# design.net
KiCad netlist of a schematic drawn in Altium Designer
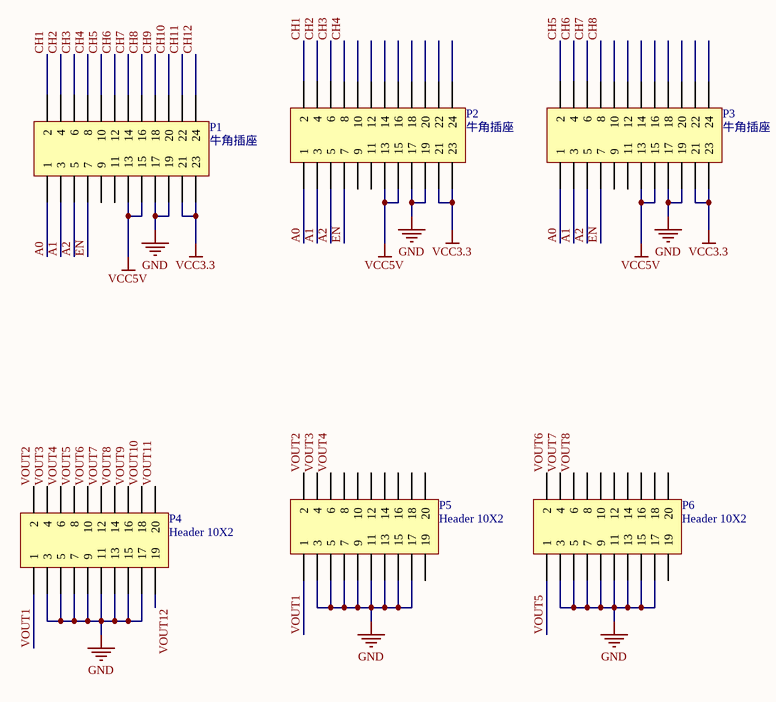
[diagram p0: 数粒机转接板.SchDoc]

(export (version "E")
  (design (tool "Eeschema 10.0.6"))
  (components
    (comp (ref "P1")
      (value "牛角插座")
      (footprint "niujiaocha24p")
      (description "Header, 12-Pin, Dual row")
      (fields (field (name "PUBLISHER") "Altium Limited"))
      (libsource (lib "Miscellaneous Connectors") (part "Header 12X2"))
    )
    (comp (ref "P2")
      (value "牛角插座")
      (footprint "niujiaocha24p")
      (description "Header, 12-Pin, Dual row")
      (fields (field (name "PUBLISHER") "Altium Limited"))
      (libsource (lib "Miscellaneous Connectors") (part "Header 12X2"))
    )
    (comp (ref "P3")
      (value "牛角插座")
      (footprint "niujiaocha24p")
      (description "Header, 12-Pin, Dual row")
      (fields (field (name "PUBLISHER") "Altium Limited"))
      (libsource (lib "Miscellaneous Connectors") (part "Header 12X2"))
    )
    (comp (ref "P4")
      (value "Header 10X2")
      (footprint "niujiaocha20p")
      (description "Header, 10-Pin, Dual row")
      (fields (field (name "PUBLISHER") "Altium Limited"))
      (libsource (lib "Miscellaneous Connectors") (part "Header 10X2"))
    )
    (comp (ref "P5")
      (value "Header 10X2")
      (footprint "niujiaocha20p")
      (description "Header, 10-Pin, Dual row")
      (fields (field (name "PUBLISHER") "Altium Limited"))
      (libsource (lib "Miscellaneous Connectors") (part "Header 10X2"))
    )
    (comp (ref "P6")
      (value "Header 10X2")
      (footprint "niujiaocha20p")
      (description "Header, 10-Pin, Dual row")
      (fields (field (name "PUBLISHER") "Altium Limited"))
      (libsource (lib "Miscellaneous Connectors") (part "Header 10X2"))
    )
  )
  (nets
    (net (code "1") (name "/A0") (class "Default")
      (node (ref "P1") (pin "1") (pinfunction "1_1") (pintype "passive"))
      (node (ref "P2") (pin "1") (pinfunction "1_1") (pintype "passive"))
      (node (ref "P3") (pin "1") (pinfunction "1_1") (pintype "passive"))
    )
    (net (code "2") (name "/A1") (class "Default")
      (node (ref "P1") (pin "3") (pinfunction "3_3") (pintype "passive"))
      (node (ref "P2") (pin "3") (pinfunction "3_3") (pintype "passive"))
      (node (ref "P3") (pin "3") (pinfunction "3_3") (pintype "passive"))
    )
    (net (code "3") (name "/A2") (class "Default")
      (node (ref "P1") (pin "5") (pinfunction "5_5") (pintype "passive"))
      (node (ref "P2") (pin "5") (pinfunction "5_5") (pintype "passive"))
      (node (ref "P3") (pin "5") (pinfunction "5_5") (pintype "passive"))
    )
    (net (code "4") (name "/CH1") (class "Default")
      (node (ref "P1") (pin "2") (pinfunction "2_2") (pintype "passive"))
      (node (ref "P2") (pin "2") (pinfunction "2_2") (pintype "passive"))
    )
    (net (code "5") (name "/CH2") (class "Default")
      (node (ref "P1") (pin "4") (pinfunction "4_4") (pintype "passive"))
      (node (ref "P2") (pin "4") (pinfunction "4_4") (pintype "passive"))
    )
    (net (code "6") (name "/CH3") (class "Default")
      (node (ref "P1") (pin "6") (pinfunction "6_6") (pintype "passive"))
      (node (ref "P2") (pin "6") (pinfunction "6_6") (pintype "passive"))
    )
    (net (code "7") (name "/CH4") (class "Default")
      (node (ref "P1") (pin "8") (pinfunction "8_8") (pintype "passive"))
      (node (ref "P2") (pin "8") (pinfunction "8_8") (pintype "passive"))
    )
    (net (code "8") (name "/CH5") (class "Default")
      (node (ref "P1") (pin "10") (pinfunction "10_10") (pintype "passive"))
      (node (ref "P3") (pin "2") (pinfunction "2_2") (pintype "passive"))
    )
    (net (code "9") (name "/CH6") (class "Default")
      (node (ref "P1") (pin "12") (pinfunction "12_12") (pintype "passive"))
      (node (ref "P3") (pin "4") (pinfunction "4_4") (pintype "passive"))
    )
    (net (code "10") (name "/CH7") (class "Default")
      (node (ref "P1") (pin "14") (pinfunction "14_14") (pintype "passive"))
      (node (ref "P3") (pin "6") (pinfunction "6_6") (pintype "passive"))
    )
    (net (code "11") (name "/CH8") (class "Default")
      (node (ref "P1") (pin "16") (pinfunction "16_16") (pintype "passive"))
      (node (ref "P3") (pin "8") (pinfunction "8_8") (pintype "passive"))
    )
    (net (code "12") (name "/CH9") (class "Default")
      (node (ref "P1") (pin "18") (pinfunction "18_18") (pintype "passive"))
    )
    (net (code "13") (name "/CH10") (class "Default")
      (node (ref "P1") (pin "20") (pinfunction "20_20") (pintype "passive"))
    )
    (net (code "14") (name "/CH11") (class "Default")
      (node (ref "P1") (pin "22") (pinfunction "22_22") (pintype "passive"))
    )
    (net (code "15") (name "/CH12") (class "Default")
      (node (ref "P1") (pin "24") (pinfunction "24_24") (pintype "passive"))
    )
    (net (code "16") (name "/EN") (class "Default")
      (node (ref "P1") (pin "7") (pinfunction "7_7") (pintype "passive"))
      (node (ref "P2") (pin "7") (pinfunction "7_7") (pintype "passive"))
      (node (ref "P3") (pin "7") (pinfunction "7_7") (pintype "passive"))
    )
    (net (code "17") (name "/VOUT1") (class "Default")
      (node (ref "P4") (pin "1") (pinfunction "1_1") (pintype "passive"))
      (node (ref "P5") (pin "1") (pinfunction "1_1") (pintype "passive"))
    )
    (net (code "18") (name "/VOUT2") (class "Default")
      (node (ref "P4") (pin "2") (pinfunction "2_2") (pintype "passive"))
      (node (ref "P5") (pin "2") (pinfunction "2_2") (pintype "passive"))
    )
    (net (code "19") (name "/VOUT3") (class "Default")
      (node (ref "P4") (pin "4") (pinfunction "4_4") (pintype "passive"))
      (node (ref "P5") (pin "4") (pinfunction "4_4") (pintype "passive"))
    )
    (net (code "20") (name "/VOUT4") (class "Default")
      (node (ref "P4") (pin "6") (pinfunction "6_6") (pintype "passive"))
      (node (ref "P5") (pin "6") (pinfunction "6_6") (pintype "passive"))
    )
    (net (code "21") (name "/VOUT5") (class "Default")
      (node (ref "P4") (pin "8") (pinfunction "8_8") (pintype "passive"))
      (node (ref "P6") (pin "1") (pinfunction "1_1") (pintype "passive"))
    )
    (net (code "22") (name "/VOUT6") (class "Default")
      (node (ref "P4") (pin "10") (pinfunction "10_10") (pintype "passive"))
      (node (ref "P6") (pin "2") (pinfunction "2_2") (pintype "passive"))
    )
    (net (code "23") (name "/VOUT7") (class "Default")
      (node (ref "P4") (pin "12") (pinfunction "12_12") (pintype "passive"))
      (node (ref "P6") (pin "4") (pinfunction "4_4") (pintype "passive"))
    )
    (net (code "24") (name "/VOUT8") (class "Default")
      (node (ref "P4") (pin "14") (pinfunction "14_14") (pintype "passive"))
      (node (ref "P6") (pin "6") (pinfunction "6_6") (pintype "passive"))
    )
    (net (code "25") (name "/VOUT9") (class "Default")
      (node (ref "P4") (pin "16") (pinfunction "16_16") (pintype "passive"))
    )
    (net (code "26") (name "/VOUT10") (class "Default")
      (node (ref "P4") (pin "18") (pinfunction "18_18") (pintype "passive"))
    )
    (net (code "27") (name "/VOUT11") (class "Default")
      (node (ref "P4") (pin "20") (pinfunction "20_20") (pintype "passive"))
    )
    (net (code "28") (name "/VOUT12") (class "Default")
      (node (ref "P4") (pin "19") (pinfunction "19_19") (pintype "passive"))
    )
    (net (code "29") (name "GND") (class "Default")
      (node (ref "P1") (pin "17") (pinfunction "17_17") (pintype "passive"))
      (node (ref "P1") (pin "19") (pinfunction "19_19") (pintype "passive"))
      (node (ref "P2") (pin "17") (pinfunction "17_17") (pintype "passive"))
      (node (ref "P2") (pin "19") (pinfunction "19_19") (pintype "passive"))
      (node (ref "P3") (pin "17") (pinfunction "17_17") (pintype "passive"))
      (node (ref "P3") (pin "19") (pinfunction "19_19") (pintype "passive"))
      (node (ref "P4") (pin "11") (pinfunction "11_11") (pintype "passive"))
      (node (ref "P4") (pin "13") (pinfunction "13_13") (pintype "passive"))
      (node (ref "P4") (pin "15") (pinfunction "15_15") (pintype "passive"))
      (node (ref "P4") (pin "17") (pinfunction "17_17") (pintype "passive"))
      (node (ref "P4") (pin "3") (pinfunction "3_3") (pintype "passive"))
      (node (ref "P4") (pin "5") (pinfunction "5_5") (pintype "passive"))
      (node (ref "P4") (pin "7") (pinfunction "7_7") (pintype "passive"))
      (node (ref "P4") (pin "9") (pinfunction "9_9") (pintype "passive"))
      (node (ref "P5") (pin "11") (pinfunction "11_11") (pintype "passive"))
      (node (ref "P5") (pin "13") (pinfunction "13_13") (pintype "passive"))
      (node (ref "P5") (pin "15") (pinfunction "15_15") (pintype "passive"))
      (node (ref "P5") (pin "17") (pinfunction "17_17") (pintype "passive"))
      (node (ref "P5") (pin "3") (pinfunction "3_3") (pintype "passive"))
      (node (ref "P5") (pin "5") (pinfunction "5_5") (pintype "passive"))
      (node (ref "P5") (pin "7") (pinfunction "7_7") (pintype "passive"))
      (node (ref "P5") (pin "9") (pinfunction "9_9") (pintype "passive"))
      (node (ref "P6") (pin "11") (pinfunction "11_11") (pintype "passive"))
      (node (ref "P6") (pin "13") (pinfunction "13_13") (pintype "passive"))
      (node (ref "P6") (pin "15") (pinfunction "15_15") (pintype "passive"))
      (node (ref "P6") (pin "17") (pinfunction "17_17") (pintype "passive"))
      (node (ref "P6") (pin "3") (pinfunction "3_3") (pintype "passive"))
      (node (ref "P6") (pin "5") (pinfunction "5_5") (pintype "passive"))
      (node (ref "P6") (pin "7") (pinfunction "7_7") (pintype "passive"))
      (node (ref "P6") (pin "9") (pinfunction "9_9") (pintype "passive"))
    )
    (net (code "30") (name "VCC3.3") (class "Default")
      (node (ref "P1") (pin "21") (pinfunction "21_21") (pintype "passive"))
      (node (ref "P1") (pin "23") (pinfunction "23_23") (pintype "passive"))
      (node (ref "P2") (pin "21") (pinfunction "21_21") (pintype "passive"))
      (node (ref "P2") (pin "23") (pinfunction "23_23") (pintype "passive"))
      (node (ref "P3") (pin "21") (pinfunction "21_21") (pintype "passive"))
      (node (ref "P3") (pin "23") (pinfunction "23_23") (pintype "passive"))
    )
    (net (code "31") (name "VCC5V") (class "Default")
      (node (ref "P1") (pin "13") (pinfunction "13_13") (pintype "passive"))
      (node (ref "P1") (pin "15") (pinfunction "15_15") (pintype "passive"))
      (node (ref "P2") (pin "13") (pinfunction "13_13") (pintype "passive"))
      (node (ref "P2") (pin "15") (pinfunction "15_15") (pintype "passive"))
      (node (ref "P3") (pin "13") (pinfunction "13_13") (pintype "passive"))
      (node (ref "P3") (pin "15") (pinfunction "15_15") (pintype "passive"))
    )
    (net (code "32") (name "unconnected-(P1-Pad9)") (class "Default")
      (node (ref "P1") (pin "9") (pinfunction "9_9") (pintype "passive"))
    )
    (net (code "33") (name "unconnected-(P1-Pad11)") (class "Default")
      (node (ref "P1") (pin "11") (pinfunction "11_11") (pintype "passive"))
    )
    (net (code "34") (name "unconnected-(P2-Pad9)") (class "Default")
      (node (ref "P2") (pin "9") (pinfunction "9_9") (pintype "passive"))
    )
    (net (code "35") (name "unconnected-(P2-Pad10)") (class "Default")
      (node (ref "P2") (pin "10") (pinfunction "10_10") (pintype "passive"))
    )
    (net (code "36") (name "unconnected-(P2-Pad11)") (class "Default")
      (node (ref "P2") (pin "11") (pinfunction "11_11") (pintype "passive"))
    )
    (net (code "37") (name "unconnected-(P2-Pad12)") (class "Default")
      (node (ref "P2") (pin "12") (pinfunction "12_12") (pintype "passive"))
    )
    (net (code "38") (name "unconnected-(P2-Pad14)") (class "Default")
      (node (ref "P2") (pin "14") (pinfunction "14_14") (pintype "passive"))
    )
    (net (code "39") (name "unconnected-(P2-Pad16)") (class "Default")
      (node (ref "P2") (pin "16") (pinfunction "16_16") (pintype "passive"))
    )
    (net (code "40") (name "unconnected-(P2-Pad18)") (class "Default")
      (node (ref "P2") (pin "18") (pinfunction "18_18") (pintype "passive"))
    )
    (net (code "41") (name "unconnected-(P2-Pad20)") (class "Default")
      (node (ref "P2") (pin "20") (pinfunction "20_20") (pintype "passive"))
    )
    (net (code "42") (name "unconnected-(P2-Pad22)") (class "Default")
      (node (ref "P2") (pin "22") (pinfunction "22_22") (pintype "passive"))
    )
    (net (code "43") (name "unconnected-(P2-Pad24)") (class "Default")
      (node (ref "P2") (pin "24") (pinfunction "24_24") (pintype "passive"))
    )
    (net (code "44") (name "unconnected-(P3-Pad9)") (class "Default")
      (node (ref "P3") (pin "9") (pinfunction "9_9") (pintype "passive"))
    )
    (net (code "45") (name "unconnected-(P3-Pad10)") (class "Default")
      (node (ref "P3") (pin "10") (pinfunction "10_10") (pintype "passive"))
    )
    (net (code "46") (name "unconnected-(P3-Pad11)") (class "Default")
      (node (ref "P3") (pin "11") (pinfunction "11_11") (pintype "passive"))
    )
    (net (code "47") (name "unconnected-(P3-Pad12)") (class "Default")
      (node (ref "P3") (pin "12") (pinfunction "12_12") (pintype "passive"))
    )
    (net (code "48") (name "unconnected-(P3-Pad14)") (class "Default")
      (node (ref "P3") (pin "14") (pinfunction "14_14") (pintype "passive"))
    )
    (net (code "49") (name "unconnected-(P3-Pad16)") (class "Default")
      (node (ref "P3") (pin "16") (pinfunction "16_16") (pintype "passive"))
    )
    (net (code "50") (name "unconnected-(P3-Pad18)") (class "Default")
      (node (ref "P3") (pin "18") (pinfunction "18_18") (pintype "passive"))
    )
    (net (code "51") (name "unconnected-(P3-Pad20)") (class "Default")
      (node (ref "P3") (pin "20") (pinfunction "20_20") (pintype "passive"))
    )
    (net (code "52") (name "unconnected-(P3-Pad22)") (class "Default")
      (node (ref "P3") (pin "22") (pinfunction "22_22") (pintype "passive"))
    )
    (net (code "53") (name "unconnected-(P3-Pad24)") (class "Default")
      (node (ref "P3") (pin "24") (pinfunction "24_24") (pintype "passive"))
    )
    (net (code "54") (name "unconnected-(P5-Pad8)") (class "Default")
      (node (ref "P5") (pin "8") (pinfunction "8_8") (pintype "passive"))
    )
    (net (code "55") (name "unconnected-(P5-Pad10)") (class "Default")
      (node (ref "P5") (pin "10") (pinfunction "10_10") (pintype "passive"))
    )
    (net (code "56") (name "unconnected-(P5-Pad12)") (class "Default")
      (node (ref "P5") (pin "12") (pinfunction "12_12") (pintype "passive"))
    )
    (net (code "57") (name "unconnected-(P5-Pad14)") (class "Default")
      (node (ref "P5") (pin "14") (pinfunction "14_14") (pintype "passive"))
    )
    (net (code "58") (name "unconnected-(P5-Pad16)") (class "Default")
      (node (ref "P5") (pin "16") (pinfunction "16_16") (pintype "passive"))
    )
    (net (code "59") (name "unconnected-(P5-Pad18)") (class "Default")
      (node (ref "P5") (pin "18") (pinfunction "18_18") (pintype "passive"))
    )
    (net (code "60") (name "unconnected-(P5-Pad19)") (class "Default")
      (node (ref "P5") (pin "19") (pinfunction "19_19") (pintype "passive"))
    )
    (net (code "61") (name "unconnected-(P5-Pad20)") (class "Default")
      (node (ref "P5") (pin "20") (pinfunction "20_20") (pintype "passive"))
    )
    (net (code "62") (name "unconnected-(P6-Pad8)") (class "Default")
      (node (ref "P6") (pin "8") (pinfunction "8_8") (pintype "passive"))
    )
    (net (code "63") (name "unconnected-(P6-Pad10)") (class "Default")
      (node (ref "P6") (pin "10") (pinfunction "10_10") (pintype "passive"))
    )
    (net (code "64") (name "unconnected-(P6-Pad12)") (class "Default")
      (node (ref "P6") (pin "12") (pinfunction "12_12") (pintype "passive"))
    )
    (net (code "65") (name "unconnected-(P6-Pad14)") (class "Default")
      (node (ref "P6") (pin "14") (pinfunction "14_14") (pintype "passive"))
    )
    (net (code "66") (name "unconnected-(P6-Pad16)") (class "Default")
      (node (ref "P6") (pin "16") (pinfunction "16_16") (pintype "passive"))
    )
    (net (code "67") (name "unconnected-(P6-Pad18)") (class "Default")
      (node (ref "P6") (pin "18") (pinfunction "18_18") (pintype "passive"))
    )
    (net (code "68") (name "unconnected-(P6-Pad19)") (class "Default")
      (node (ref "P6") (pin "19") (pinfunction "19_19") (pintype "passive"))
    )
    (net (code "69") (name "unconnected-(P6-Pad20)") (class "Default")
      (node (ref "P6") (pin "20") (pinfunction "20_20") (pintype "passive"))
    )
  )
)
